# Ethernet_Phy.net
KiCad netlist of a schematic drawn in Altium Designer
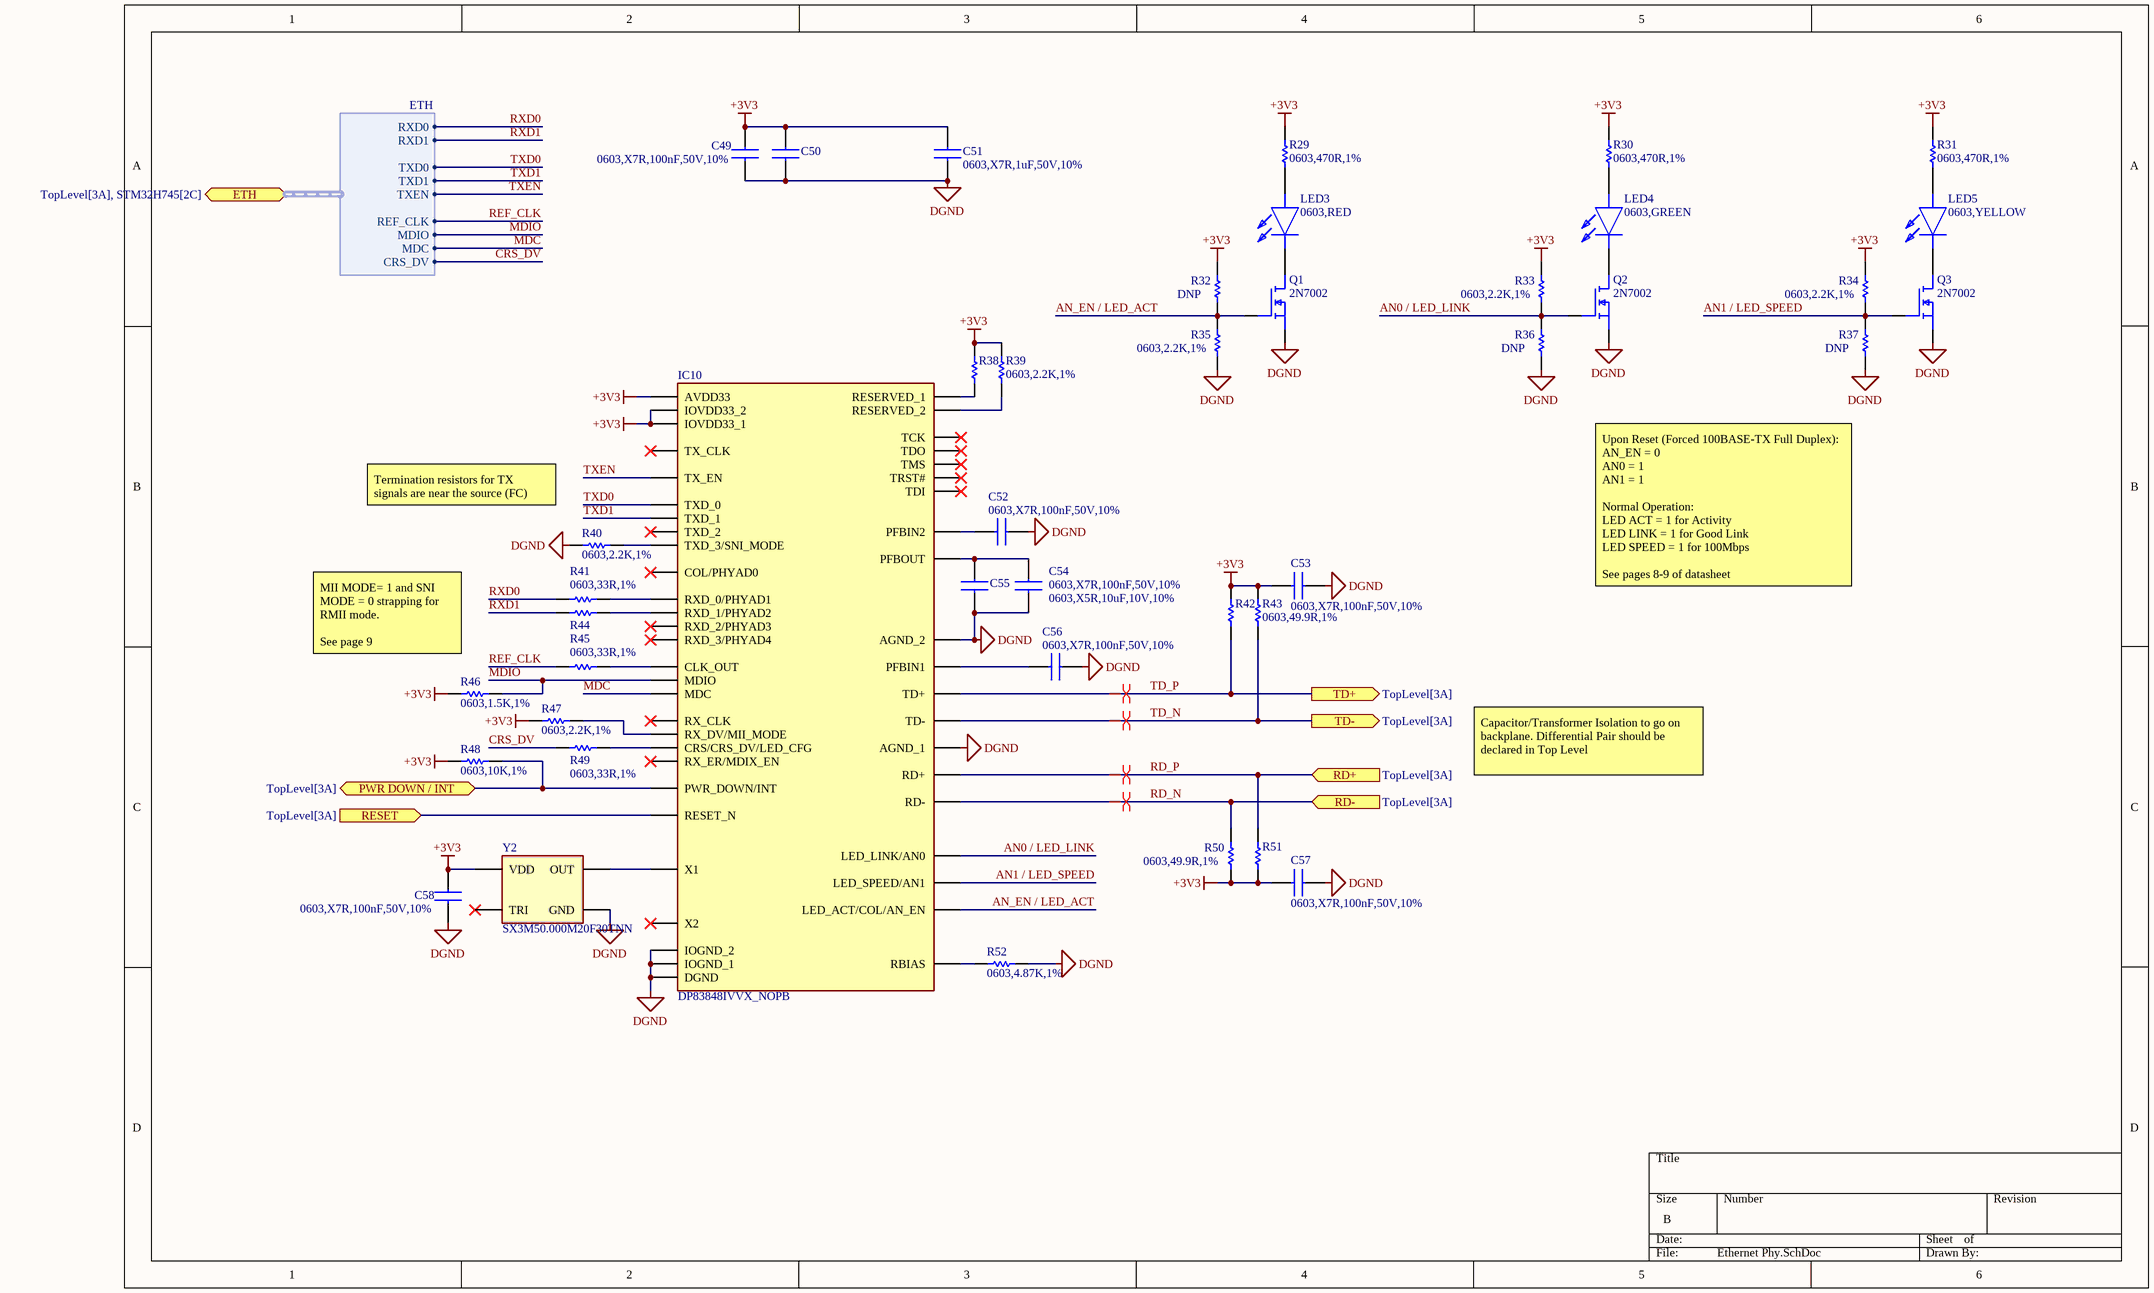
[diagram p0: Ethernet Phy.SchDoc]

(export (version "E")
  (design (tool "Eeschema 10.0.6"))
  (components
    (comp (ref "C49")
      (value "0603,X7R,100nF,50V,10%")
      (footprint "CAPC1608X90N")
      (description "50V 100nF X7R ±10% 0603 Multilayer Ceramic Capacitors MLCC - SMD/SMT ROHS")
      (fields (field (name "LCSC PART #") "C14663") (field (name "MANU PART #") "CC0603KRX7R9BB104"))
      (libsource (lib "flight-controller") (part "CC0603KRX7R9BB104"))
    )
    (comp (ref "C50")
      (value "0603,X7R,100nF,50V,10%")
      (footprint "CAPC1608X90N")
      (description "50V 100nF X7R ±10% 0603 Multilayer Ceramic Capacitors MLCC - SMD/SMT ROHS")
      (fields (field (name "LCSC PART #") "C14663") (field (name "MANU PART #") "CC0603KRX7R9BB104"))
      (libsource (lib "flight-controller") (part "CC0603KRX7R9BB104"))
    )
    (comp (ref "C51")
      (value "0603,X7R,1uF,50V,10%")
      (footprint "CAPC1608X90N")
      (description "50V 1uF X7R ±10% 0603 Multilayer Ceramic Capacitors MLCC - SMD/SMT ROHS")
      (fields (field (name "LCSC PART #") "C15849") (field (name "MANU PART #") "CL10A105KB8NNNC"))
      (libsource (lib "flight-controller") (part "CL10A105KB8NNNC"))
    )
    (comp (ref "C52")
      (value "0603,X7R,100nF,50V,10%")
      (footprint "CAPC1608X90N")
      (description "50V 100nF X7R ±10% 0603 Multilayer Ceramic Capacitors MLCC - SMD/SMT ROHS")
      (fields (field (name "LCSC PART #") "C14663") (field (name "MANU PART #") "CC0603KRX7R9BB104"))
      (libsource (lib "flight-controller") (part "CC0603KRX7R9BB104"))
    )
    (comp (ref "C53")
      (value "0603,X7R,100nF,50V,10%")
      (footprint "CAPC1608X90N")
      (description "50V 100nF X7R ±10% 0603 Multilayer Ceramic Capacitors MLCC - SMD/SMT ROHS")
      (fields (field (name "LCSC PART #") "C14663") (field (name "MANU PART #") "CC0603KRX7R9BB104"))
      (libsource (lib "flight-controller") (part "CC0603KRX7R9BB104"))
    )
    (comp (ref "C54")
      (value "0603,X7R,100nF,50V,10%")
      (footprint "CAPC1608X90N")
      (description "50V 100nF X7R ±10% 0603 Multilayer Ceramic Capacitors MLCC - SMD/SMT ROHS")
      (fields (field (name "LCSC PART #") "C14663") (field (name "MANU PART #") "CC0603KRX7R9BB104"))
      (libsource (lib "flight-controller") (part "CC0603KRX7R9BB104"))
    )
    (comp (ref "C55")
      (value "0603,X5R,10uF,10V,10%")
      (footprint "CAPC1608X90N")
      (description "10uF ±10% 10V Ceramic Capacitor X5R 0603")
      (fields (field (name "LCSC PART #") "C19702") (field (name "MANU PART #") "CL10A106KP8NNNC"))
      (libsource (lib "flight-controller") (part "CL10A106KP8NNNC"))
    )
    (comp (ref "C56")
      (value "0603,X7R,100nF,50V,10%")
      (footprint "CAPC1608X90N")
      (description "50V 100nF X7R ±10% 0603 Multilayer Ceramic Capacitors MLCC - SMD/SMT ROHS")
      (fields (field (name "LCSC PART #") "C14663") (field (name "MANU PART #") "CC0603KRX7R9BB104"))
      (libsource (lib "flight-controller") (part "CC0603KRX7R9BB104"))
    )
    (comp (ref "C57")
      (value "0603,X7R,100nF,50V,10%")
      (footprint "CAPC1608X90N")
      (description "50V 100nF X7R ±10% 0603 Multilayer Ceramic Capacitors MLCC - SMD/SMT ROHS")
      (fields (field (name "LCSC PART #") "C14663") (field (name "MANU PART #") "CC0603KRX7R9BB104"))
      (libsource (lib "flight-controller") (part "CC0603KRX7R9BB104"))
    )
    (comp (ref "C58")
      (value "0603,X7R,100nF,50V,10%")
      (footprint "CAPC1608X90N")
      (description "50V 100nF X7R ±10% 0603 Multilayer Ceramic Capacitors MLCC - SMD/SMT ROHS")
      (fields (field (name "LCSC PART #") "C14663") (field (name "MANU PART #") "CC0603KRX7R9BB104"))
      (libsource (lib "flight-controller") (part "CC0603KRX7R9BB104"))
    )
    (comp (ref "IC10")
      (value "DP83848IVVX_NOPB")
      (footprint "QFP50P900X900X160-48N")
      (description "Single Port 10/100 Mb/s Ethernet Physical Layer Transceiver")
      (fields (field (name "MANU PART #") "DP83848IVVX/NOPB") (field (name "LCSC PART #") "C12082"))
      (libsource (lib "flight-controller") (part "DP83848IVVX_NOPB"))
    )
    (comp (ref "LED3")
      (value "0603,RED")
      (footprint "LEDC1608X36N")
      (fields (field (name "MANU PART #") "KT-0603R") (field (name "LCSC PART #") "C2286"))
      (libsource (lib "flight-controller") (part "KT-0603R"))
    )
    (comp (ref "LED4")
      (value "0603,GREEN")
      (footprint "LEDC1608X36N")
      (description "Green LED Indication - Discrete 2.2V 0603")
      (fields (field (name "MANU PART #") "SML-E12P8WT86") (field (name "LCSC PART #") "C126319"))
      (libsource (lib "flight-controller") (part "SML-E12P8WT86"))
    )
    (comp (ref "LED5")
      (value "0603,YELLOW")
      (footprint "LEDC1608X36N")
      (description "Yellow LED Indication - Discrete 2.2V 0603")
      (fields (field (name "MANU PART #") "SML-D12Y1WT86") (field (name "LCSC PART #") "C253534"))
      (libsource (lib "flight-controller") (part "SML-D12Y1WT86"))
    )
    (comp (ref "Q1")
      (value "2N7002")
      (footprint "SOT95P230X110-3N")
      (description "N-Channel 60V 300mA 830mW Surface Mount SOT-23")
      (fields (field (name "LCSC PART #") "C8545"))
      (libsource (lib "flight-controller") (part "2N7002"))
    )
    (comp (ref "Q2")
      (value "2N7002")
      (footprint "SOT95P230X110-3N")
      (description "N-Channel 60V 300mA 830mW Surface Mount SOT-23")
      (fields (field (name "LCSC PART #") "C8545"))
      (libsource (lib "flight-controller") (part "2N7002"))
    )
    (comp (ref "Q3")
      (value "2N7002")
      (footprint "SOT95P230X110-3N")
      (description "N-Channel 60V 300mA 830mW Surface Mount SOT-23")
      (fields (field (name "LCSC PART #") "C8545"))
      (libsource (lib "flight-controller") (part "2N7002"))
    )
    (comp (ref "R29")
      (value "0603,470R,1%")
      (footprint "RESC1608X90N")
      (fields (field (name "LCSC PART #") "C23179") (field (name "MANU PART #") "0603WAF4700T5E"))
      (libsource (lib "flight-controller") (part "0603WAF4700T5E"))
    )
    (comp (ref "R30")
      (value "0603,470R,1%")
      (footprint "RESC1608X90N")
      (fields (field (name "LCSC PART #") "C23179") (field (name "MANU PART #") "0603WAF4700T5E"))
      (libsource (lib "flight-controller") (part "0603WAF4700T5E"))
    )
    (comp (ref "R31")
      (value "0603,470R,1%")
      (footprint "RESC1608X90N")
      (fields (field (name "LCSC PART #") "C23179") (field (name "MANU PART #") "0603WAF4700T5E"))
      (libsource (lib "flight-controller") (part "0603WAF4700T5E"))
    )
    (comp (ref "R32")
      (value "DNP")
      (footprint "RESC1608X90N")
      (description "2.2kΩ ±1% 100mW 0603 Thick Film Resistor")
      (fields (field (name "LCSC PART #") "C4190") (field (name "MANU PART #") "0603WAF2201T5E"))
      (libsource (lib "flight-controller") (part "0603WAF2201T5E"))
    )
    (comp (ref "R33")
      (value "0603,2.2K,1%")
      (footprint "RESC1608X90N")
      (description "2.2kΩ ±1% 100mW 0603 Thick Film Resistor")
      (fields (field (name "LCSC PART #") "C4190") (field (name "MANU PART #") "0603WAF2201T5E"))
      (libsource (lib "flight-controller") (part "0603WAF2201T5E"))
    )
    (comp (ref "R34")
      (value "0603,2.2K,1%")
      (footprint "RESC1608X90N")
      (description "2.2kΩ ±1% 100mW 0603 Thick Film Resistor")
      (fields (field (name "LCSC PART #") "C4190") (field (name "MANU PART #") "0603WAF2201T5E"))
      (libsource (lib "flight-controller") (part "0603WAF2201T5E"))
    )
    (comp (ref "R35")
      (value "0603,2.2K,1%")
      (footprint "RESC1608X90N")
      (description "2.2kΩ ±1% 100mW 0603 Thick Film Resistor")
      (fields (field (name "LCSC PART #") "C4190") (field (name "MANU PART #") "0603WAF2201T5E"))
      (libsource (lib "flight-controller") (part "0603WAF2201T5E"))
    )
    (comp (ref "R36")
      (value "DNP")
      (footprint "RESC1608X90N")
      (description "2.2kΩ ±1% 100mW 0603 Thick Film Resistor")
      (fields (field (name "LCSC PART #") "C4190") (field (name "MANU PART #") "0603WAF2201T5E"))
      (libsource (lib "flight-controller") (part "0603WAF2201T5E"))
    )
    (comp (ref "R37")
      (value "DNP")
      (footprint "RESC1608X90N")
      (description "2.2kΩ ±1% 100mW 0603 Thick Film Resistor")
      (fields (field (name "LCSC PART #") "C4190") (field (name "MANU PART #") "0603WAF2201T5E"))
      (libsource (lib "flight-controller") (part "0603WAF2201T5E"))
    )
    (comp (ref "R38")
      (value "0603,2.2K,1%")
      (footprint "RESC1608X90N")
      (description "2.2kΩ ±1% 100mW 0603 Thick Film Resistor")
      (fields (field (name "LCSC PART #") "C4190") (field (name "MANU PART #") "0603WAF2201T5E"))
      (libsource (lib "flight-controller") (part "0603WAF2201T5E"))
    )
    (comp (ref "R39")
      (value "0603,2.2K,1%")
      (footprint "RESC1608X90N")
      (description "2.2kΩ ±1% 100mW 0603 Thick Film Resistor")
      (fields (field (name "LCSC PART #") "C4190") (field (name "MANU PART #") "0603WAF2201T5E"))
      (libsource (lib "flight-controller") (part "0603WAF2201T5E"))
    )
    (comp (ref "R40")
      (value "0603,2.2K,1%")
      (footprint "RESC1608X90N")
      (description "2.2kΩ ±1% 100mW 0603 Thick Film Resistor")
      (fields (field (name "LCSC PART #") "C4190") (field (name "MANU PART #") "0603WAF2201T5E"))
      (libsource (lib "flight-controller") (part "0603WAF2201T5E"))
    )
    (comp (ref "R41")
      (value "0603,33R,1%")
      (footprint "RESC1608X90N")
      (description "100mW 33Ω 75V Thick Film Resistor ±100ppm/℃ ±1% 0603 Chip Resistor - Surface Mount RoHS")
      (fields (field (name "LCSC PART #") "C23140") (field (name "MANU PART #") "0603WAF330JT5E"))
      (libsource (lib "flight-controller") (part "0603WAF330JT5E"))
    )
    (comp (ref "R42")
      (value "0603,49.9R,1%")
      (footprint "RESC1608X90N")
      (fields (field (name "LCSC PART #") "C23185") (field (name "MANU PART #") "0603WAF499JT5E"))
      (libsource (lib "flight-controller") (part "0603WAF499JT5E"))
    )
    (comp (ref "R43")
      (value "0603,49.9R,1%")
      (footprint "RESC1608X90N")
      (fields (field (name "LCSC PART #") "C23185") (field (name "MANU PART #") "0603WAF499JT5E"))
      (libsource (lib "flight-controller") (part "0603WAF499JT5E"))
    )
    (comp (ref "R44")
      (value "0603,33R,1%")
      (footprint "RESC1608X90N")
      (description "100mW 33Ω 75V Thick Film Resistor ±100ppm/℃ ±1% 0603 Chip Resistor - Surface Mount RoHS")
      (fields (field (name "LCSC PART #") "C23140") (field (name "MANU PART #") "0603WAF330JT5E"))
      (libsource (lib "flight-controller") (part "0603WAF330JT5E"))
    )
    (comp (ref "R45")
      (value "0603,33R,1%")
      (footprint "RESC1608X90N")
      (description "100mW 33Ω 75V Thick Film Resistor ±100ppm/℃ ±1% 0603 Chip Resistor - Surface Mount RoHS")
      (fields (field (name "LCSC PART #") "C23140") (field (name "MANU PART #") "0603WAF330JT5E"))
      (libsource (lib "flight-controller") (part "0603WAF330JT5E"))
    )
    (comp (ref "R46")
      (value "0603,1.5K,1%")
      (footprint "RESC1608X90N")
      (description "100mW 1.5kΩ 75V Thick Film Resistor ±100ppm/℃ ±1% 0603 Chip Resistor - Surface Mount RoHS")
      (fields (field (name "LCSC PART #") "C22843") (field (name "MANU PART #") "0603WAF1501T5E"))
      (libsource (lib "flight-controller") (part "0603WAF1501T5E"))
    )
    (comp (ref "R47")
      (value "0603,2.2K,1%")
      (footprint "RESC1608X90N")
      (description "2.2kΩ ±1% 100mW 0603 Thick Film Resistor")
      (fields (field (name "LCSC PART #") "C4190") (field (name "MANU PART #") "0603WAF2201T5E"))
      (libsource (lib "flight-controller") (part "0603WAF2201T5E"))
    )
    (comp (ref "R48")
      (value "0603,10K,1%")
      (footprint "RESC1608X90N")
      (description "100mW Thick Film Resistor 75V ±100ppm/℃ ±1% 10kΩ 0603 Chip Resistor - Surface Mount ROHS")
      (fields (field (name "LCSC PART #") "C25804") (field (name "MANU PART #") "0603WAF1002T5E"))
      (libsource (lib "flight-controller") (part "0603WAF1002T5E"))
    )
    (comp (ref "R49")
      (value "0603,33R,1%")
      (footprint "RESC1608X90N")
      (description "100mW 33Ω 75V Thick Film Resistor ±100ppm/℃ ±1% 0603 Chip Resistor - Surface Mount RoHS")
      (fields (field (name "LCSC PART #") "C23140") (field (name "MANU PART #") "0603WAF330JT5E"))
      (libsource (lib "flight-controller") (part "0603WAF330JT5E"))
    )
    (comp (ref "R50")
      (value "0603,49.9R,1%")
      (footprint "RESC1608X90N")
      (fields (field (name "LCSC PART #") "C23185") (field (name "MANU PART #") "0603WAF499JT5E"))
      (libsource (lib "flight-controller") (part "0603WAF499JT5E"))
    )
    (comp (ref "R51")
      (value "0603,49.9R,1%")
      (footprint "RESC1608X90N")
      (fields (field (name "LCSC PART #") "C23185") (field (name "MANU PART #") "0603WAF499JT5E"))
      (libsource (lib "flight-controller") (part "0603WAF499JT5E"))
    )
    (comp (ref "R52")
      (value "0603,4.87K,1%")
      (footprint "RESC1608X55N")
      (description "4.87kΩ 100mW 75V Thick Film Resistor ±100ppm/℃ ±1% 0603 Chip Resistor - Surface Mount RoHS")
      (fields (field (name "LCSC PART #") "C137709") (field (name "MANU PART #") "RC0603FR-074K87L"))
      (libsource (lib "flight-controller") (part "RC0603FR-074K87L"))
    )
    (comp (ref "Y2")
      (value "SX3M50.000M20F30TNN")
      (footprint "SX3M50_000M20F30TNN")
      (description "Oscillator 50MHz ±20ppm CMOS 1.62V~3.63V SMD3225-4P")
      (fields (field (name "LCSC PART #") "C2901592"))
      (libsource (lib "flight-controller") (part "SX3M50.000M20F30TNN"))
    )
  )
  (nets
    (net (code "2") (name "+3V3") (class "Default")
      (node (ref "C49") (pin "2") (pinfunction "2_2") (pintype "passive"))
      (node (ref "C50") (pin "2") (pinfunction "2_2") (pintype "passive"))
      (node (ref "C51") (pin "2") (pinfunction "2_2") (pintype "passive"))
      (node (ref "C53") (pin "2") (pinfunction "2_2") (pintype "passive"))
      (node (ref "C57") (pin "2") (pinfunction "2_2") (pintype "passive"))
      (node (ref "C58") (pin "2") (pinfunction "2_2") (pintype "passive"))
      (node (ref "IC10") (pin "22") (pinfunction "AVDD33_22") (pintype "passive"))
      (node (ref "IC10") (pin "32") (pinfunction "IOVDD33_1_32") (pintype "passive"))
      (node (ref "IC10") (pin "48") (pinfunction "IOVDD33_2_48") (pintype "passive"))
      (node (ref "R29") (pin "2") (pinfunction "2_2") (pintype "passive"))
      (node (ref "R30") (pin "2") (pinfunction "2_2") (pintype "passive"))
      (node (ref "R31") (pin "2") (pinfunction "2_2") (pintype "passive"))
      (node (ref "R32") (pin "2") (pinfunction "2_2") (pintype "passive"))
      (node (ref "R33") (pin "2") (pinfunction "2_2") (pintype "passive"))
      (node (ref "R34") (pin "2") (pinfunction "2_2") (pintype "passive"))
      (node (ref "R38") (pin "2") (pinfunction "2_2") (pintype "passive"))
      (node (ref "R39") (pin "2") (pinfunction "2_2") (pintype "passive"))
      (node (ref "R42") (pin "2") (pinfunction "2_2") (pintype "passive"))
      (node (ref "R43") (pin "2") (pinfunction "2_2") (pintype "passive"))
      (node (ref "R46") (pin "1") (pinfunction "1_1") (pintype "passive"))
      (node (ref "R47") (pin "1") (pinfunction "1_1") (pintype "passive"))
      (node (ref "R48") (pin "1") (pinfunction "1_1") (pintype "passive"))
      (node (ref "R50") (pin "1") (pinfunction "1_1") (pintype "passive"))
      (node (ref "R51") (pin "1") (pinfunction "1_1") (pintype "passive"))
      (node (ref "Y2") (pin "4") (pinfunction "VDD_4") (pintype "passive"))
    )
    (net (code "3") (name "/AN0 {slash} LED_LINK") (class "Default")
      (node (ref "IC10") (pin "28") (pinfunction "LED_LINK/AN0_28") (pintype "passive"))
      (node (ref "Q2") (pin "1") (pinfunction "G_1") (pintype "passive"))
      (node (ref "R33") (pin "1") (pinfunction "1_1") (pintype "passive"))
      (node (ref "R36") (pin "2") (pinfunction "2_2") (pintype "passive"))
    )
    (net (code "4") (name "/AN1 {slash} LED_SPEED") (class "Default")
      (node (ref "IC10") (pin "27") (pinfunction "LED_SPEED/AN1_27") (pintype "passive"))
      (node (ref "Q3") (pin "1") (pinfunction "G_1") (pintype "passive"))
      (node (ref "R34") (pin "1") (pinfunction "1_1") (pintype "passive"))
      (node (ref "R37") (pin "2") (pinfunction "2_2") (pintype "passive"))
    )
    (net (code "5") (name "/AN_EN {slash} LED_ACT") (class "Default")
      (node (ref "IC10") (pin "26") (pinfunction "LED_ACT/COL/AN_EN_26") (pintype "passive"))
      (node (ref "Q1") (pin "1") (pinfunction "G_1") (pintype "passive"))
      (node (ref "R32") (pin "1") (pinfunction "1_1") (pintype "passive"))
      (node (ref "R35") (pin "2") (pinfunction "2_2") (pintype "passive"))
    )
    (net (code "6") (name "/CRS_DV") (class "Default")
      (node (ref "R49") (pin "1") (pinfunction "1_1") (pintype "passive"))
    )
    (net (code "7") (name "/MDC") (class "Default")
      (node (ref "IC10") (pin "31") (pinfunction "MDC_31") (pintype "passive"))
    )
    (net (code "8") (name "/MDIO") (class "Default")
      (node (ref "IC10") (pin "30") (pinfunction "MDIO_30") (pintype "passive"))
      (node (ref "R46") (pin "2") (pinfunction "2_2") (pintype "passive"))
    )
    (net (code "9") (name "/PWR DOWN {slash} INT") (class "Default")
      (node (ref "IC10") (pin "7") (pinfunction "PWR_DOWN/INT_7") (pintype "passive"))
      (node (ref "R48") (pin "2") (pinfunction "2_2") (pintype "passive"))
    )
    (net (code "10") (name "/RD_N") (class "Default")
      (node (ref "IC10") (pin "13") (pinfunction "RD-_13") (pintype "passive"))
      (node (ref "R50") (pin "2") (pinfunction "2_2") (pintype "passive"))
    )
    (net (code "11") (name "/RD_P") (class "Default")
      (node (ref "IC10") (pin "14") (pinfunction "RD+_14") (pintype "passive"))
      (node (ref "R51") (pin "2") (pinfunction "2_2") (pintype "passive"))
    )
    (net (code "12") (name "/REF_CLK") (class "Default")
      (node (ref "R45") (pin "1") (pinfunction "1_1") (pintype "passive"))
    )
    (net (code "13") (name "/RESET") (class "Default")
      (node (ref "IC10") (pin "29") (pinfunction "RESET_N_29") (pintype "passive"))
    )
    (net (code "14") (name "/RXD0") (class "Default")
      (node (ref "R41") (pin "1") (pinfunction "1_1") (pintype "passive"))
    )
    (net (code "15") (name "/RXD1") (class "Default")
      (node (ref "R44") (pin "1") (pinfunction "1_1") (pintype "passive"))
    )
    (net (code "16") (name "/TD_N") (class "Default")
      (node (ref "IC10") (pin "16") (pinfunction "TD-_16") (pintype "passive"))
      (node (ref "R43") (pin "1") (pinfunction "1_1") (pintype "passive"))
    )
    (net (code "17") (name "/TD_P") (class "Default")
      (node (ref "IC10") (pin "17") (pinfunction "TD+_17") (pintype "passive"))
      (node (ref "R42") (pin "1") (pinfunction "1_1") (pintype "passive"))
    )
    (net (code "18") (name "/TXD0") (class "Default")
      (node (ref "IC10") (pin "3") (pinfunction "TXD_0_3") (pintype "passive"))
    )
    (net (code "19") (name "/TXD1") (class "Default")
      (node (ref "IC10") (pin "4") (pinfunction "TXD_1_4") (pintype "passive"))
    )
    (net (code "20") (name "/TXEN") (class "Default")
      (node (ref "IC10") (pin "2") (pinfunction "TX_EN_2") (pintype "passive"))
    )
    (net (code "22") (name "DGND") (class "Default")
      (node (ref "C49") (pin "1") (pinfunction "1_1") (pintype "passive"))
      (node (ref "C50") (pin "1") (pinfunction "1_1") (pintype "passive"))
      (node (ref "C51") (pin "1") (pinfunction "1_1") (pintype "passive"))
      (node (ref "C52") (pin "1") (pinfunction "1_1") (pintype "passive"))
      (node (ref "C53") (pin "1") (pinfunction "1_1") (pintype "passive"))
      (node (ref "C54") (pin "1") (pinfunction "1_1") (pintype "passive"))
      (node (ref "C55") (pin "1") (pinfunction "1_1") (pintype "passive"))
      (node (ref "C56") (pin "2") (pinfunction "2_2") (pintype "passive"))
      (node (ref "C57") (pin "1") (pinfunction "1_1") (pintype "passive"))
      (node (ref "C58") (pin "1") (pinfunction "1_1") (pintype "passive"))
      (node (ref "IC10") (pin "15") (pinfunction "AGND_1_15") (pintype "passive"))
      (node (ref "IC10") (pin "19") (pinfunction "AGND_2_19") (pintype "passive"))
      (node (ref "IC10") (pin "35") (pinfunction "IOGND_1_35") (pintype "passive"))
      (node (ref "IC10") (pin "36") (pinfunction "DGND_36") (pintype "passive"))
      (node (ref "IC10") (pin "47") (pinfunction "IOGND_2_47") (pintype "passive"))
      (node (ref "Q1") (pin "2") (pinfunction "S_2") (pintype "passive"))
      (node (ref "Q2") (pin "2") (pinfunction "S_2") (pintype "passive"))
      (node (ref "Q3") (pin "2") (pinfunction "S_2") (pintype "passive"))
      (node (ref "R35") (pin "1") (pinfunction "1_1") (pintype "passive"))
      (node (ref "R36") (pin "1") (pinfunction "1_1") (pintype "passive"))
      (node (ref "R37") (pin "1") (pinfunction "1_1") (pintype "passive"))
      (node (ref "R40") (pin "1") (pinfunction "1_1") (pintype "passive"))
      (node (ref "R52") (pin "2") (pinfunction "2_2") (pintype "passive"))
      (node (ref "Y2") (pin "2") (pinfunction "GND_2") (pintype "passive"))
    )
    (net (code "23") (name "Net-(IC10-CLK_OUT)") (class "Default")
      (node (ref "IC10") (pin "25") (pinfunction "CLK_OUT_25") (pintype "passive"))
      (node (ref "R45") (pin "2") (pinfunction "2_2") (pintype "passive"))
    )
    (net (code "24") (name "Net-(IC10-CRS{slash}CRS_DV{slash}LED_CFG)") (class "Default")
      (node (ref "IC10") (pin "40") (pinfunction "CRS/CRS_DV/LED_CFG_40") (pintype "passive"))
      (node (ref "R49") (pin "2") (pinfunction "2_2") (pintype "passive"))
    )
    (net (code "25") (name "Net-(IC10-PFBIN1)") (class "Default")
      (node (ref "C56") (pin "1") (pinfunction "1_1") (pintype "passive"))
      (node (ref "IC10") (pin "18") (pinfunction "PFBIN1_18") (pintype "passive"))
    )
    (net (code "26") (name "Net-(IC10-PFBIN2)") (class "Default")
      (node (ref "C52") (pin "2") (pinfunction "2_2") (pintype "passive"))
      (node (ref "IC10") (pin "37") (pinfunction "PFBIN2_37") (pintype "passive"))
    )
    (net (code "27") (name "Net-(IC10-PFBOUT)") (class "Default")
      (node (ref "C54") (pin "2") (pinfunction "2_2") (pintype "passive"))
      (node (ref "C55") (pin "2") (pinfunction "2_2") (pintype "passive"))
      (node (ref "IC10") (pin "23") (pinfunction "PFBOUT_23") (pintype "passive"))
    )
    (net (code "28") (name "Net-(IC10-RBIAS)") (class "Default")
      (node (ref "IC10") (pin "24") (pinfunction "RBIAS_24") (pintype "passive"))
      (node (ref "R52") (pin "1") (pinfunction "1_1") (pintype "passive"))
    )
    (net (code "29") (name "Net-(IC10-RESERVED_1)") (class "Default")
      (node (ref "IC10") (pin "20") (pinfunction "RESERVED_1_20") (pintype "passive"))
      (node (ref "R38") (pin "1") (pinfunction "1_1") (pintype "passive"))
    )
    (net (code "30") (name "Net-(IC10-RESERVED_2)") (class "Default")
      (node (ref "IC10") (pin "21") (pinfunction "RESERVED_2_21") (pintype "passive"))
      (node (ref "R39") (pin "1") (pinfunction "1_1") (pintype "passive"))
    )
    (net (code "31") (name "Net-(IC10-RXD_0{slash}PHYAD1)") (class "Default")
      (node (ref "IC10") (pin "43") (pinfunction "RXD_0/PHYAD1_43") (pintype "passive"))
      (node (ref "R41") (pin "2") (pinfunction "2_2") (pintype "passive"))
    )
    (net (code "32") (name "Net-(IC10-RXD_1{slash}PHYAD2)") (class "Default")
      (node (ref "IC10") (pin "44") (pinfunction "RXD_1/PHYAD2_44") (pintype "passive"))
      (node (ref "R44") (pin "2") (pinfunction "2_2") (pintype "passive"))
    )
    (net (code "33") (name "Net-(IC10-RX_DV{slash}MII_MODE)") (class "Default")
      (node (ref "IC10") (pin "39") (pinfunction "RX_DV/MII_MODE_39") (pintype "passive"))
      (node (ref "R47") (pin "2") (pinfunction "2_2") (pintype "passive"))
    )
    (net (code "34") (name "Net-(IC10-TXD_3{slash}SNI_MODE)") (class "Default")
      (node (ref "IC10") (pin "6") (pinfunction "TXD_3/SNI_MODE_6") (pintype "passive"))
      (node (ref "R40") (pin "2") (pinfunction "2_2") (pintype "passive"))
    )
    (net (code "35") (name "Net-(IC10-X1)") (class "Default")
      (node (ref "IC10") (pin "34") (pinfunction "X1_34") (pintype "passive"))
      (node (ref "Y2") (pin "3") (pinfunction "OUT_3") (pintype "passive"))
    )
    (net (code "36") (name "Net-(LED3-A)") (class "Default")
      (node (ref "LED3") (pin "2") (pinfunction "A_2") (pintype "passive"))
      (node (ref "R29") (pin "1") (pinfunction "1_1") (pintype "passive"))
    )
    (net (code "37") (name "Net-(LED3-K)") (class "Default")
      (node (ref "LED3") (pin "1") (pinfunction "K_1") (pintype "passive"))
      (node (ref "Q1") (pin "3") (pinfunction "D_3") (pintype "passive"))
    )
    (net (code "38") (name "Net-(LED4-A)") (class "Default")
      (node (ref "LED4") (pin "2") (pinfunction "A_2") (pintype "passive"))
      (node (ref "R30") (pin "1") (pinfunction "1_1") (pintype "passive"))
    )
    (net (code "39") (name "Net-(LED4-K)") (class "Default")
      (node (ref "LED4") (pin "1") (pinfunction "K_1") (pintype "passive"))
      (node (ref "Q2") (pin "3") (pinfunction "D_3") (pintype "passive"))
    )
    (net (code "40") (name "Net-(LED5-A)") (class "Default")
      (node (ref "LED5") (pin "2") (pinfunction "A_2") (pintype "passive"))
      (node (ref "R31") (pin "1") (pinfunction "1_1") (pintype "passive"))
    )
    (net (code "41") (name "Net-(LED5-K)") (class "Default")
      (node (ref "LED5") (pin "1") (pinfunction "K_1") (pintype "passive"))
      (node (ref "Q3") (pin "3") (pinfunction "D_3") (pintype "passive"))
    )
    (net (code "42") (name "unconnected-(IC10-COL{slash}PHYAD0-Pad42)") (class "Default")
      (node (ref "IC10") (pin "42") (pinfunction "COL/PHYAD0_42") (pintype "passive+no_connect"))
    )
    (net (code "43") (name "unconnected-(IC10-RXD_2{slash}PHYAD3-Pad45)") (class "Default")
      (node (ref "IC10") (pin "45") (pinfunction "RXD_2/PHYAD3_45") (pintype "passive+no_connect"))
    )
    (net (code "44") (name "unconnected-(IC10-RXD_3{slash}PHYAD4-Pad46)") (class "Default")
      (node (ref "IC10") (pin "46") (pinfunction "RXD_3/PHYAD4_46") (pintype "passive+no_connect"))
    )
    (net (code "45") (name "unconnected-(IC10-RX_CLK-Pad38)") (class "Default")
      (node (ref "IC10") (pin "38") (pinfunction "RX_CLK_38") (pintype "passive+no_connect"))
    )
    (net (code "46") (name "unconnected-(IC10-RX_ER{slash}MDIX_EN-Pad41)") (class "Default")
      (node (ref "IC10") (pin "41") (pinfunction "RX_ER/MDIX_EN_41") (pintype "passive+no_connect"))
    )
    (net (code "47") (name "unconnected-(IC10-TCK-Pad8)") (class "Default")
      (node (ref "IC10") (pin "8") (pinfunction "TCK_8") (pintype "passive+no_connect"))
    )
    (net (code "48") (name "unconnected-(IC10-TDI-Pad12)") (class "Default")
      (node (ref "IC10") (pin "12") (pinfunction "TDI_12") (pintype "passive+no_connect"))
    )
    (net (code "49") (name "unconnected-(IC10-TDO-Pad9)") (class "Default")
      (node (ref "IC10") (pin "9") (pinfunction "TDO_9") (pintype "passive+no_connect"))
    )
    (net (code "50") (name "unconnected-(IC10-TMS-Pad10)") (class "Default")
      (node (ref "IC10") (pin "10") (pinfunction "TMS_10") (pintype "passive+no_connect"))
    )
    (net (code "51") (name "unconnected-(IC10-TRST#-Pad11)") (class "Default")
      (node (ref "IC10") (pin "11") (pinfunction "TRST#_11") (pintype "passive+no_connect"))
    )
    (net (code "52") (name "unconnected-(IC10-TXD_2-Pad5)") (class "Default")
      (node (ref "IC10") (pin "5") (pinfunction "TXD_2_5") (pintype "passive+no_connect"))
    )
    (net (code "53") (name "unconnected-(IC10-TX_CLK-Pad1)") (class "Default")
      (node (ref "IC10") (pin "1") (pinfunction "TX_CLK_1") (pintype "passive+no_connect"))
    )
    (net (code "54") (name "unconnected-(IC10-X2-Pad33)") (class "Default")
      (node (ref "IC10") (pin "33") (pinfunction "X2_33") (pintype "passive+no_connect"))
    )
    (net (code "55") (name "unconnected-(Y2-TRI-Pad1)") (class "Default")
      (node (ref "Y2") (pin "1") (pinfunction "TRI_1") (pintype "passive+no_connect"))
    )
  )
)
